# TLC5971.net
KiCad netlist of a schematic drawn in EAGLE
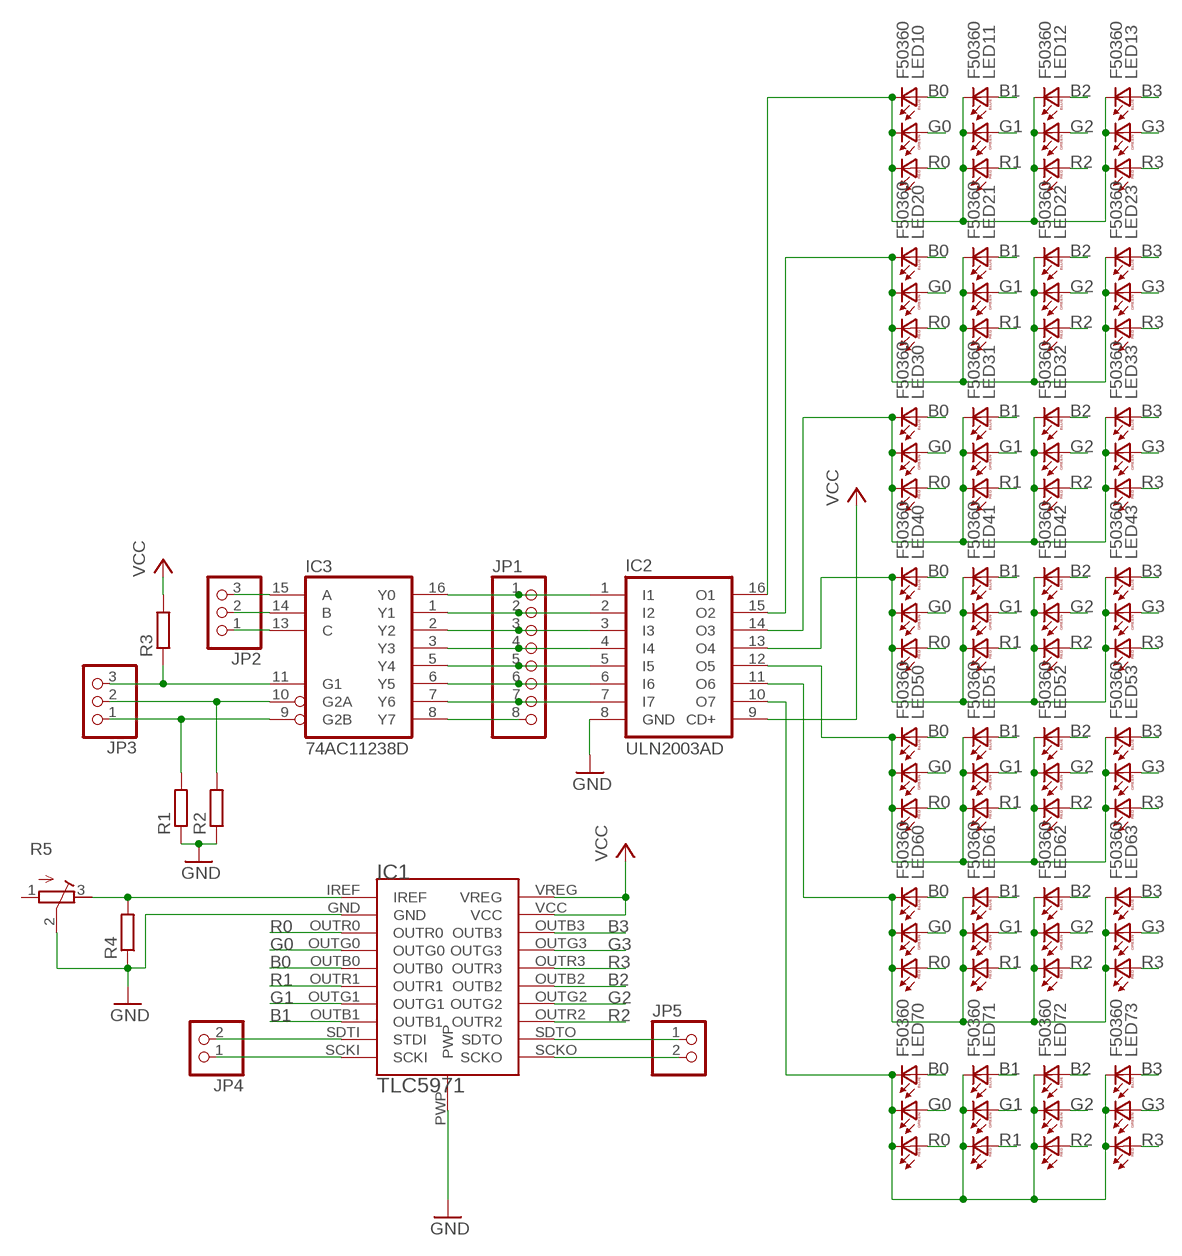
[diagram p0: schematic, sheet 1]

(export (version "E")
  (design (tool "Eeschema 10.0.6"))
  (components
    (comp (ref "IC1")
      (value "TLC5971")
      (footprint "eagle-import:HTSSOP-20(PWP)")
      (libsource (lib "eagle-import") (part "TLC5971"))
    )
    (comp (ref "IC2")
      (value "ULN2003AD")
      (footprint "eagle-import:SO16")
      (libsource (lib "eagle-import") (part "ULN2003AD"))
    )
    (comp (ref "IC3")
      (value "74AC11238D")
      (footprint "eagle-import:SO16")
      (libsource (lib "eagle-import") (part "74AC11238D"))
    )
    (comp (ref "JP1")
      (value "PINHD-1X8")
      (footprint "eagle-import:1X08")
      (libsource (lib "eagle-import") (part "PINHD-1X8"))
    )
    (comp (ref "JP2")
      (value "PINHD-1X3")
      (footprint "eagle-import:1X03")
      (libsource (lib "eagle-import") (part "PINHD-1X3"))
    )
    (comp (ref "JP3")
      (value "PINHD-1X3")
      (footprint "eagle-import:1X03")
      (libsource (lib "eagle-import") (part "PINHD-1X3"))
    )
    (comp (ref "JP4")
      (value "PINHD-1X2")
      (footprint "eagle-import:1X02")
      (libsource (lib "eagle-import") (part "PINHD-1X2"))
    )
    (comp (ref "JP5")
      (value "PINHD-1X2")
      (footprint "eagle-import:1X02")
      (libsource (lib "eagle-import") (part "PINHD-1X2"))
    )
    (comp (ref "LED10")
      (value "F50360")
      (footprint "eagle-import:F50360")
      (libsource (lib "eagle-import") (part "F50360"))
    )
    (comp (ref "LED11")
      (value "F50360")
      (footprint "eagle-import:F50360")
      (libsource (lib "eagle-import") (part "F50360"))
    )
    (comp (ref "LED12")
      (value "F50360")
      (footprint "eagle-import:F50360")
      (libsource (lib "eagle-import") (part "F50360"))
    )
    (comp (ref "LED13")
      (value "F50360")
      (footprint "eagle-import:F50360")
      (libsource (lib "eagle-import") (part "F50360"))
    )
    (comp (ref "LED20")
      (value "F50360")
      (footprint "eagle-import:F50360")
      (libsource (lib "eagle-import") (part "F50360"))
    )
    (comp (ref "LED21")
      (value "F50360")
      (footprint "eagle-import:F50360")
      (libsource (lib "eagle-import") (part "F50360"))
    )
    (comp (ref "LED22")
      (value "F50360")
      (footprint "eagle-import:F50360")
      (libsource (lib "eagle-import") (part "F50360"))
    )
    (comp (ref "LED23")
      (value "F50360")
      (footprint "eagle-import:F50360")
      (libsource (lib "eagle-import") (part "F50360"))
    )
    (comp (ref "LED30")
      (value "F50360")
      (footprint "eagle-import:F50360")
      (libsource (lib "eagle-import") (part "F50360"))
    )
    (comp (ref "LED31")
      (value "F50360")
      (footprint "eagle-import:F50360")
      (libsource (lib "eagle-import") (part "F50360"))
    )
    (comp (ref "LED32")
      (value "F50360")
      (footprint "eagle-import:F50360")
      (libsource (lib "eagle-import") (part "F50360"))
    )
    (comp (ref "LED33")
      (value "F50360")
      (footprint "eagle-import:F50360")
      (libsource (lib "eagle-import") (part "F50360"))
    )
    (comp (ref "LED40")
      (value "F50360")
      (footprint "eagle-import:F50360")
      (libsource (lib "eagle-import") (part "F50360"))
    )
    (comp (ref "LED41")
      (value "F50360")
      (footprint "eagle-import:F50360")
      (libsource (lib "eagle-import") (part "F50360"))
    )
    (comp (ref "LED42")
      (value "F50360")
      (footprint "eagle-import:F50360")
      (libsource (lib "eagle-import") (part "F50360"))
    )
    (comp (ref "LED43")
      (value "F50360")
      (footprint "eagle-import:F50360")
      (libsource (lib "eagle-import") (part "F50360"))
    )
    (comp (ref "LED50")
      (value "F50360")
      (footprint "eagle-import:F50360")
      (libsource (lib "eagle-import") (part "F50360"))
    )
    (comp (ref "LED51")
      (value "F50360")
      (footprint "eagle-import:F50360")
      (libsource (lib "eagle-import") (part "F50360"))
    )
    (comp (ref "LED52")
      (value "F50360")
      (footprint "eagle-import:F50360")
      (libsource (lib "eagle-import") (part "F50360"))
    )
    (comp (ref "LED53")
      (value "F50360")
      (footprint "eagle-import:F50360")
      (libsource (lib "eagle-import") (part "F50360"))
    )
    (comp (ref "LED60")
      (value "F50360")
      (footprint "eagle-import:F50360")
      (libsource (lib "eagle-import") (part "F50360"))
    )
    (comp (ref "LED61")
      (value "F50360")
      (footprint "eagle-import:F50360")
      (libsource (lib "eagle-import") (part "F50360"))
    )
    (comp (ref "LED62")
      (value "F50360")
      (footprint "eagle-import:F50360")
      (libsource (lib "eagle-import") (part "F50360"))
    )
    (comp (ref "LED63")
      (value "F50360")
      (footprint "eagle-import:F50360")
      (libsource (lib "eagle-import") (part "F50360"))
    )
    (comp (ref "LED70")
      (value "F50360")
      (footprint "eagle-import:F50360")
      (libsource (lib "eagle-import") (part "F50360"))
    )
    (comp (ref "LED71")
      (value "F50360")
      (footprint "eagle-import:F50360")
      (libsource (lib "eagle-import") (part "F50360"))
    )
    (comp (ref "LED72")
      (value "F50360")
      (footprint "eagle-import:F50360")
      (libsource (lib "eagle-import") (part "F50360"))
    )
    (comp (ref "LED73")
      (value "F50360")
      (footprint "eagle-import:F50360")
      (libsource (lib "eagle-import") (part "F50360"))
    )
    (comp (ref "R1")
      (value "R-EU_M0805")
      (footprint "eagle-import:M0805")
      (libsource (lib "eagle-import") (part "R-EU_M0805"))
    )
    (comp (ref "R2")
      (value "R-EU_M0805")
      (footprint "eagle-import:M0805")
      (libsource (lib "eagle-import") (part "R-EU_M0805"))
    )
    (comp (ref "R3")
      (value "R-EU_M0805")
      (footprint "eagle-import:M0805")
      (libsource (lib "eagle-import") (part "R-EU_M0805"))
    )
    (comp (ref "R4")
      (value "R-EU_M0805")
      (footprint "eagle-import:M0805")
      (libsource (lib "eagle-import") (part "R-EU_M0805"))
    )
    (comp (ref "R5")
      (value "R-TRIMM74W")
      (footprint "eagle-import:RTRIM74W")
      (libsource (lib "eagle-import") (part "R-TRIMM74W"))
    )
  )
  (nets
    (net (code "1") (name "/B0") (class "Default")
      (node (ref "IC1") (pin "OUTB0") (pinfunction "OUTB0_OUTB0") (pintype "output"))
      (node (ref "LED10") (pin "BA") (pinfunction "BA_BA") (pintype "passive"))
      (node (ref "LED20") (pin "BA") (pinfunction "BA_BA") (pintype "passive"))
      (node (ref "LED30") (pin "BA") (pinfunction "BA_BA") (pintype "passive"))
      (node (ref "LED40") (pin "BA") (pinfunction "BA_BA") (pintype "passive"))
      (node (ref "LED50") (pin "BA") (pinfunction "BA_BA") (pintype "passive"))
      (node (ref "LED60") (pin "BA") (pinfunction "BA_BA") (pintype "passive"))
      (node (ref "LED70") (pin "BA") (pinfunction "BA_BA") (pintype "passive"))
    )
    (net (code "2") (name "/B1") (class "Default")
      (node (ref "IC1") (pin "OUTB1") (pinfunction "OUTB1_OUTB1") (pintype "output"))
      (node (ref "LED11") (pin "BA") (pinfunction "BA_BA") (pintype "passive"))
      (node (ref "LED21") (pin "BA") (pinfunction "BA_BA") (pintype "passive"))
      (node (ref "LED31") (pin "BA") (pinfunction "BA_BA") (pintype "passive"))
      (node (ref "LED41") (pin "BA") (pinfunction "BA_BA") (pintype "passive"))
      (node (ref "LED51") (pin "BA") (pinfunction "BA_BA") (pintype "passive"))
      (node (ref "LED61") (pin "BA") (pinfunction "BA_BA") (pintype "passive"))
      (node (ref "LED71") (pin "BA") (pinfunction "BA_BA") (pintype "passive"))
    )
    (net (code "3") (name "/B2") (class "Default")
      (node (ref "IC1") (pin "OUTB2") (pinfunction "OUTB2_OUTB2") (pintype "output"))
      (node (ref "LED12") (pin "BA") (pinfunction "BA_BA") (pintype "passive"))
      (node (ref "LED22") (pin "BA") (pinfunction "BA_BA") (pintype "passive"))
      (node (ref "LED32") (pin "BA") (pinfunction "BA_BA") (pintype "passive"))
      (node (ref "LED42") (pin "BA") (pinfunction "BA_BA") (pintype "passive"))
      (node (ref "LED52") (pin "BA") (pinfunction "BA_BA") (pintype "passive"))
      (node (ref "LED62") (pin "BA") (pinfunction "BA_BA") (pintype "passive"))
      (node (ref "LED72") (pin "BA") (pinfunction "BA_BA") (pintype "passive"))
    )
    (net (code "4") (name "/B3") (class "Default")
      (node (ref "IC1") (pin "OUTB3") (pinfunction "OUTB3_OUTB3") (pintype "output"))
      (node (ref "LED13") (pin "BA") (pinfunction "BA_BA") (pintype "passive"))
      (node (ref "LED23") (pin "BA") (pinfunction "BA_BA") (pintype "passive"))
      (node (ref "LED33") (pin "BA") (pinfunction "BA_BA") (pintype "passive"))
      (node (ref "LED43") (pin "BA") (pinfunction "BA_BA") (pintype "passive"))
      (node (ref "LED53") (pin "BA") (pinfunction "BA_BA") (pintype "passive"))
      (node (ref "LED63") (pin "BA") (pinfunction "BA_BA") (pintype "passive"))
      (node (ref "LED73") (pin "BA") (pinfunction "BA_BA") (pintype "passive"))
    )
    (net (code "5") (name "/G0") (class "Default")
      (node (ref "IC1") (pin "OUTG0") (pinfunction "OUTG0_OUTG0") (pintype "output"))
      (node (ref "LED10") (pin "GA") (pinfunction "GA_GA") (pintype "passive"))
      (node (ref "LED20") (pin "GA") (pinfunction "GA_GA") (pintype "passive"))
      (node (ref "LED30") (pin "GA") (pinfunction "GA_GA") (pintype "passive"))
      (node (ref "LED40") (pin "GA") (pinfunction "GA_GA") (pintype "passive"))
      (node (ref "LED50") (pin "GA") (pinfunction "GA_GA") (pintype "passive"))
      (node (ref "LED60") (pin "GA") (pinfunction "GA_GA") (pintype "passive"))
      (node (ref "LED70") (pin "GA") (pinfunction "GA_GA") (pintype "passive"))
    )
    (net (code "6") (name "/G1") (class "Default")
      (node (ref "IC1") (pin "OUTG1") (pinfunction "OUTG1_OUTG1") (pintype "output"))
      (node (ref "LED11") (pin "GA") (pinfunction "GA_GA") (pintype "passive"))
      (node (ref "LED21") (pin "GA") (pinfunction "GA_GA") (pintype "passive"))
      (node (ref "LED31") (pin "GA") (pinfunction "GA_GA") (pintype "passive"))
      (node (ref "LED41") (pin "GA") (pinfunction "GA_GA") (pintype "passive"))
      (node (ref "LED51") (pin "GA") (pinfunction "GA_GA") (pintype "passive"))
      (node (ref "LED61") (pin "GA") (pinfunction "GA_GA") (pintype "passive"))
      (node (ref "LED71") (pin "GA") (pinfunction "GA_GA") (pintype "passive"))
    )
    (net (code "7") (name "/G2") (class "Default")
      (node (ref "IC1") (pin "OUTG2") (pinfunction "OUTG2_OUTG2") (pintype "output"))
      (node (ref "LED12") (pin "GA") (pinfunction "GA_GA") (pintype "passive"))
      (node (ref "LED22") (pin "GA") (pinfunction "GA_GA") (pintype "passive"))
      (node (ref "LED32") (pin "GA") (pinfunction "GA_GA") (pintype "passive"))
      (node (ref "LED42") (pin "GA") (pinfunction "GA_GA") (pintype "passive"))
      (node (ref "LED52") (pin "GA") (pinfunction "GA_GA") (pintype "passive"))
      (node (ref "LED62") (pin "GA") (pinfunction "GA_GA") (pintype "passive"))
      (node (ref "LED72") (pin "GA") (pinfunction "GA_GA") (pintype "passive"))
    )
    (net (code "8") (name "/G3") (class "Default")
      (node (ref "IC1") (pin "OUTG3") (pinfunction "OUTG3_OUTG3") (pintype "output"))
      (node (ref "LED13") (pin "GA") (pinfunction "GA_GA") (pintype "passive"))
      (node (ref "LED23") (pin "GA") (pinfunction "GA_GA") (pintype "passive"))
      (node (ref "LED33") (pin "GA") (pinfunction "GA_GA") (pintype "passive"))
      (node (ref "LED43") (pin "GA") (pinfunction "GA_GA") (pintype "passive"))
      (node (ref "LED53") (pin "GA") (pinfunction "GA_GA") (pintype "passive"))
      (node (ref "LED63") (pin "GA") (pinfunction "GA_GA") (pintype "passive"))
      (node (ref "LED73") (pin "GA") (pinfunction "GA_GA") (pintype "passive"))
    )
    (net (code "9") (name "/R0") (class "Default")
      (node (ref "IC1") (pin "OUTR0") (pinfunction "OUTR0_OUTR0") (pintype "output"))
      (node (ref "LED10") (pin "RA") (pinfunction "RA_RA") (pintype "passive"))
      (node (ref "LED20") (pin "RA") (pinfunction "RA_RA") (pintype "passive"))
      (node (ref "LED30") (pin "RA") (pinfunction "RA_RA") (pintype "passive"))
      (node (ref "LED40") (pin "RA") (pinfunction "RA_RA") (pintype "passive"))
      (node (ref "LED50") (pin "RA") (pinfunction "RA_RA") (pintype "passive"))
      (node (ref "LED60") (pin "RA") (pinfunction "RA_RA") (pintype "passive"))
      (node (ref "LED70") (pin "RA") (pinfunction "RA_RA") (pintype "passive"))
    )
    (net (code "10") (name "/R1") (class "Default")
      (node (ref "IC1") (pin "OUTR1") (pinfunction "OUTR1_OUTR1") (pintype "output"))
      (node (ref "LED11") (pin "RA") (pinfunction "RA_RA") (pintype "passive"))
      (node (ref "LED21") (pin "RA") (pinfunction "RA_RA") (pintype "passive"))
      (node (ref "LED31") (pin "RA") (pinfunction "RA_RA") (pintype "passive"))
      (node (ref "LED41") (pin "RA") (pinfunction "RA_RA") (pintype "passive"))
      (node (ref "LED51") (pin "RA") (pinfunction "RA_RA") (pintype "passive"))
      (node (ref "LED61") (pin "RA") (pinfunction "RA_RA") (pintype "passive"))
      (node (ref "LED71") (pin "RA") (pinfunction "RA_RA") (pintype "passive"))
    )
    (net (code "11") (name "/R2") (class "Default")
      (node (ref "IC1") (pin "OUTR2") (pinfunction "OUTR2_OUTR2") (pintype "output"))
      (node (ref "LED12") (pin "RA") (pinfunction "RA_RA") (pintype "passive"))
      (node (ref "LED22") (pin "RA") (pinfunction "RA_RA") (pintype "passive"))
      (node (ref "LED32") (pin "RA") (pinfunction "RA_RA") (pintype "passive"))
      (node (ref "LED42") (pin "RA") (pinfunction "RA_RA") (pintype "passive"))
      (node (ref "LED52") (pin "RA") (pinfunction "RA_RA") (pintype "passive"))
      (node (ref "LED62") (pin "RA") (pinfunction "RA_RA") (pintype "passive"))
      (node (ref "LED72") (pin "RA") (pinfunction "RA_RA") (pintype "passive"))
    )
    (net (code "12") (name "/R3") (class "Default")
      (node (ref "IC1") (pin "OUTR3") (pinfunction "OUTR3_OUTR3") (pintype "bidirectional"))
      (node (ref "LED13") (pin "RA") (pinfunction "RA_RA") (pintype "passive"))
      (node (ref "LED23") (pin "RA") (pinfunction "RA_RA") (pintype "passive"))
      (node (ref "LED33") (pin "RA") (pinfunction "RA_RA") (pintype "passive"))
      (node (ref "LED43") (pin "RA") (pinfunction "RA_RA") (pintype "passive"))
      (node (ref "LED53") (pin "RA") (pinfunction "RA_RA") (pintype "passive"))
      (node (ref "LED63") (pin "RA") (pinfunction "RA_RA") (pintype "passive"))
      (node (ref "LED73") (pin "RA") (pinfunction "RA_RA") (pintype "passive"))
    )
    (net (code "13") (name "GND") (class "Default")
      (node (ref "IC1") (pin "GND") (pinfunction "GND_GND") (pintype "power_in"))
      (node (ref "IC1") (pin "PWP") (pinfunction "PWP_PWP") (pintype "bidirectional"))
      (node (ref "IC2") (pin "8") (pinfunction "GND_8") (pintype "power_in"))
      (node (ref "R1") (pin "1") (pinfunction "1_1") (pintype "passive"))
      (node (ref "R2") (pin "1") (pinfunction "1_1") (pintype "passive"))
      (node (ref "R4") (pin "1") (pinfunction "1_1") (pintype "passive"))
      (node (ref "R5") (pin "2") (pinfunction "S_2") (pintype "passive"))
    )
    (net (code "14") (name "Net-(IC1-PadSCKI)") (class "Default")
      (node (ref "IC1") (pin "SCKI") (pinfunction "SCKI_SCKI") (pintype "bidirectional"))
      (node (ref "JP4") (pin "1") (pinfunction "1_1") (pintype "passive"))
    )
    (net (code "15") (name "Net-(IC1-PadSCKO)") (class "Default")
      (node (ref "IC1") (pin "SCKO") (pinfunction "SCKO_SCKO") (pintype "bidirectional"))
      (node (ref "JP5") (pin "2") (pinfunction "2_2") (pintype "passive"))
    )
    (net (code "16") (name "Net-(IC1-PadSDTO)") (class "Default")
      (node (ref "IC1") (pin "SDTO") (pinfunction "SDTO_SDTO") (pintype "bidirectional"))
      (node (ref "JP5") (pin "1") (pinfunction "1_1") (pintype "passive"))
    )
    (net (code "17") (name "Net-(IC1-STDI)") (class "Default")
      (node (ref "IC1") (pin "SDTI") (pinfunction "STDI_SDTI") (pintype "bidirectional"))
      (node (ref "JP4") (pin "2") (pinfunction "2_2") (pintype "passive"))
    )
    (net (code "18") (name "Net-(IC2-I1)") (class "Default")
      (node (ref "IC2") (pin "1") (pinfunction "I1_1") (pintype "input"))
      (node (ref "IC3") (pin "16") (pinfunction "Y0_16") (pintype "output"))
      (node (ref "JP1") (pin "1") (pinfunction "1_1") (pintype "passive"))
    )
    (net (code "19") (name "Net-(IC2-I2)") (class "Default")
      (node (ref "IC2") (pin "2") (pinfunction "I2_2") (pintype "input"))
      (node (ref "IC3") (pin "1") (pinfunction "Y1_1") (pintype "output"))
      (node (ref "JP1") (pin "2") (pinfunction "2_2") (pintype "passive"))
    )
    (net (code "20") (name "Net-(IC2-I3)") (class "Default")
      (node (ref "IC2") (pin "3") (pinfunction "I3_3") (pintype "input"))
      (node (ref "IC3") (pin "2") (pinfunction "Y2_2") (pintype "output"))
      (node (ref "JP1") (pin "3") (pinfunction "3_3") (pintype "passive"))
    )
    (net (code "21") (name "Net-(IC2-I4)") (class "Default")
      (node (ref "IC2") (pin "4") (pinfunction "I4_4") (pintype "input"))
      (node (ref "IC3") (pin "3") (pinfunction "Y3_3") (pintype "output"))
      (node (ref "JP1") (pin "4") (pinfunction "4_4") (pintype "passive"))
    )
    (net (code "22") (name "Net-(IC2-I5)") (class "Default")
      (node (ref "IC2") (pin "5") (pinfunction "I5_5") (pintype "input"))
      (node (ref "IC3") (pin "5") (pinfunction "Y4_5") (pintype "output"))
      (node (ref "JP1") (pin "5") (pinfunction "5_5") (pintype "passive"))
    )
    (net (code "23") (name "Net-(IC2-I6)") (class "Default")
      (node (ref "IC2") (pin "6") (pinfunction "I6_6") (pintype "input"))
      (node (ref "IC3") (pin "6") (pinfunction "Y5_6") (pintype "output"))
      (node (ref "JP1") (pin "6") (pinfunction "6_6") (pintype "passive"))
    )
    (net (code "24") (name "Net-(IC2-I7)") (class "Default")
      (node (ref "IC2") (pin "7") (pinfunction "I7_7") (pintype "input"))
      (node (ref "IC3") (pin "7") (pinfunction "Y6_7") (pintype "output"))
      (node (ref "JP1") (pin "7") (pinfunction "7_7") (pintype "passive"))
    )
    (net (code "25") (name "Net-(IC2-O1)") (class "Default")
      (node (ref "IC2") (pin "16") (pinfunction "O1_16") (pintype "open_collector"))
      (node (ref "LED10") (pin "BC") (pinfunction "BC_BC") (pintype "passive"))
      (node (ref "LED10") (pin "GC") (pinfunction "GC_GC") (pintype "passive"))
      (node (ref "LED10") (pin "RC") (pinfunction "RC_RC") (pintype "passive"))
      (node (ref "LED11") (pin "BC") (pinfunction "BC_BC") (pintype "passive"))
      (node (ref "LED11") (pin "GC") (pinfunction "GC_GC") (pintype "passive"))
      (node (ref "LED11") (pin "RC") (pinfunction "RC_RC") (pintype "passive"))
      (node (ref "LED12") (pin "BC") (pinfunction "BC_BC") (pintype "passive"))
      (node (ref "LED12") (pin "GC") (pinfunction "GC_GC") (pintype "passive"))
      (node (ref "LED12") (pin "RC") (pinfunction "RC_RC") (pintype "passive"))
      (node (ref "LED13") (pin "BC") (pinfunction "BC_BC") (pintype "passive"))
      (node (ref "LED13") (pin "GC") (pinfunction "GC_GC") (pintype "passive"))
      (node (ref "LED13") (pin "RC") (pinfunction "RC_RC") (pintype "passive"))
    )
    (net (code "26") (name "Net-(IC2-O2)") (class "Default")
      (node (ref "IC2") (pin "15") (pinfunction "O2_15") (pintype "open_collector"))
      (node (ref "LED20") (pin "BC") (pinfunction "BC_BC") (pintype "passive"))
      (node (ref "LED20") (pin "GC") (pinfunction "GC_GC") (pintype "passive"))
      (node (ref "LED20") (pin "RC") (pinfunction "RC_RC") (pintype "passive"))
      (node (ref "LED21") (pin "BC") (pinfunction "BC_BC") (pintype "passive"))
      (node (ref "LED21") (pin "GC") (pinfunction "GC_GC") (pintype "passive"))
      (node (ref "LED21") (pin "RC") (pinfunction "RC_RC") (pintype "passive"))
      (node (ref "LED22") (pin "BC") (pinfunction "BC_BC") (pintype "passive"))
      (node (ref "LED22") (pin "GC") (pinfunction "GC_GC") (pintype "passive"))
      (node (ref "LED22") (pin "RC") (pinfunction "RC_RC") (pintype "passive"))
      (node (ref "LED23") (pin "BC") (pinfunction "BC_BC") (pintype "passive"))
      (node (ref "LED23") (pin "GC") (pinfunction "GC_GC") (pintype "passive"))
      (node (ref "LED23") (pin "RC") (pinfunction "RC_RC") (pintype "passive"))
    )
    (net (code "27") (name "Net-(IC2-O3)") (class "Default")
      (node (ref "IC2") (pin "14") (pinfunction "O3_14") (pintype "open_collector"))
      (node (ref "LED30") (pin "BC") (pinfunction "BC_BC") (pintype "passive"))
      (node (ref "LED30") (pin "GC") (pinfunction "GC_GC") (pintype "passive"))
      (node (ref "LED30") (pin "RC") (pinfunction "RC_RC") (pintype "passive"))
      (node (ref "LED31") (pin "BC") (pinfunction "BC_BC") (pintype "passive"))
      (node (ref "LED31") (pin "GC") (pinfunction "GC_GC") (pintype "passive"))
      (node (ref "LED31") (pin "RC") (pinfunction "RC_RC") (pintype "passive"))
      (node (ref "LED32") (pin "BC") (pinfunction "BC_BC") (pintype "passive"))
      (node (ref "LED32") (pin "GC") (pinfunction "GC_GC") (pintype "passive"))
      (node (ref "LED32") (pin "RC") (pinfunction "RC_RC") (pintype "passive"))
      (node (ref "LED33") (pin "BC") (pinfunction "BC_BC") (pintype "passive"))
      (node (ref "LED33") (pin "GC") (pinfunction "GC_GC") (pintype "passive"))
      (node (ref "LED33") (pin "RC") (pinfunction "RC_RC") (pintype "passive"))
    )
    (net (code "28") (name "Net-(IC2-O4)") (class "Default")
      (node (ref "IC2") (pin "13") (pinfunction "O4_13") (pintype "open_collector"))
      (node (ref "LED40") (pin "BC") (pinfunction "BC_BC") (pintype "passive"))
      (node (ref "LED40") (pin "GC") (pinfunction "GC_GC") (pintype "passive"))
      (node (ref "LED40") (pin "RC") (pinfunction "RC_RC") (pintype "passive"))
      (node (ref "LED41") (pin "BC") (pinfunction "BC_BC") (pintype "passive"))
      (node (ref "LED41") (pin "GC") (pinfunction "GC_GC") (pintype "passive"))
      (node (ref "LED41") (pin "RC") (pinfunction "RC_RC") (pintype "passive"))
      (node (ref "LED42") (pin "BC") (pinfunction "BC_BC") (pintype "passive"))
      (node (ref "LED42") (pin "GC") (pinfunction "GC_GC") (pintype "passive"))
      (node (ref "LED42") (pin "RC") (pinfunction "RC_RC") (pintype "passive"))
      (node (ref "LED43") (pin "BC") (pinfunction "BC_BC") (pintype "passive"))
      (node (ref "LED43") (pin "GC") (pinfunction "GC_GC") (pintype "passive"))
      (node (ref "LED43") (pin "RC") (pinfunction "RC_RC") (pintype "passive"))
    )
    (net (code "29") (name "Net-(IC2-O5)") (class "Default")
      (node (ref "IC2") (pin "12") (pinfunction "O5_12") (pintype "open_collector"))
      (node (ref "LED50") (pin "BC") (pinfunction "BC_BC") (pintype "passive"))
      (node (ref "LED50") (pin "GC") (pinfunction "GC_GC") (pintype "passive"))
      (node (ref "LED50") (pin "RC") (pinfunction "RC_RC") (pintype "passive"))
      (node (ref "LED51") (pin "BC") (pinfunction "BC_BC") (pintype "passive"))
      (node (ref "LED51") (pin "GC") (pinfunction "GC_GC") (pintype "passive"))
      (node (ref "LED51") (pin "RC") (pinfunction "RC_RC") (pintype "passive"))
      (node (ref "LED52") (pin "BC") (pinfunction "BC_BC") (pintype "passive"))
      (node (ref "LED52") (pin "GC") (pinfunction "GC_GC") (pintype "passive"))
      (node (ref "LED52") (pin "RC") (pinfunction "RC_RC") (pintype "passive"))
      (node (ref "LED53") (pin "BC") (pinfunction "BC_BC") (pintype "passive"))
      (node (ref "LED53") (pin "GC") (pinfunction "GC_GC") (pintype "passive"))
      (node (ref "LED53") (pin "RC") (pinfunction "RC_RC") (pintype "passive"))
    )
    (net (code "30") (name "Net-(IC2-O6)") (class "Default")
      (node (ref "IC2") (pin "11") (pinfunction "O6_11") (pintype "open_collector"))
      (node (ref "LED60") (pin "BC") (pinfunction "BC_BC") (pintype "passive"))
      (node (ref "LED60") (pin "GC") (pinfunction "GC_GC") (pintype "passive"))
      (node (ref "LED60") (pin "RC") (pinfunction "RC_RC") (pintype "passive"))
      (node (ref "LED61") (pin "BC") (pinfunction "BC_BC") (pintype "passive"))
      (node (ref "LED61") (pin "GC") (pinfunction "GC_GC") (pintype "passive"))
      (node (ref "LED61") (pin "RC") (pinfunction "RC_RC") (pintype "passive"))
      (node (ref "LED62") (pin "BC") (pinfunction "BC_BC") (pintype "passive"))
      (node (ref "LED62") (pin "GC") (pinfunction "GC_GC") (pintype "passive"))
      (node (ref "LED62") (pin "RC") (pinfunction "RC_RC") (pintype "passive"))
      (node (ref "LED63") (pin "BC") (pinfunction "BC_BC") (pintype "passive"))
      (node (ref "LED63") (pin "GC") (pinfunction "GC_GC") (pintype "passive"))
      (node (ref "LED63") (pin "RC") (pinfunction "RC_RC") (pintype "passive"))
    )
    (net (code "31") (name "Net-(IC2-O7)") (class "Default")
      (node (ref "IC2") (pin "10") (pinfunction "O7_10") (pintype "open_collector"))
      (node (ref "LED70") (pin "BC") (pinfunction "BC_BC") (pintype "passive"))
      (node (ref "LED70") (pin "GC") (pinfunction "GC_GC") (pintype "passive"))
      (node (ref "LED70") (pin "RC") (pinfunction "RC_RC") (pintype "passive"))
      (node (ref "LED71") (pin "BC") (pinfunction "BC_BC") (pintype "passive"))
      (node (ref "LED71") (pin "GC") (pinfunction "GC_GC") (pintype "passive"))
      (node (ref "LED71") (pin "RC") (pinfunction "RC_RC") (pintype "passive"))
      (node (ref "LED72") (pin "BC") (pinfunction "BC_BC") (pintype "passive"))
      (node (ref "LED72") (pin "GC") (pinfunction "GC_GC") (pintype "passive"))
      (node (ref "LED72") (pin "RC") (pinfunction "RC_RC") (pintype "passive"))
      (node (ref "LED73") (pin "BC") (pinfunction "BC_BC") (pintype "passive"))
      (node (ref "LED73") (pin "GC") (pinfunction "GC_GC") (pintype "passive"))
      (node (ref "LED73") (pin "RC") (pinfunction "RC_RC") (pintype "passive"))
    )
    (net (code "32") (name "Net-(IC3A-A)") (class "Default")
      (node (ref "IC3") (pin "15") (pinfunction "A_15") (pintype "input"))
      (node (ref "JP2") (pin "3") (pinfunction "3_3") (pintype "passive"))
    )
    (net (code "33") (name "Net-(IC3A-B)") (class "Default")
      (node (ref "IC3") (pin "14") (pinfunction "B_14") (pintype "input"))
      (node (ref "JP2") (pin "2") (pinfunction "2_2") (pintype "passive"))
    )
    (net (code "34") (name "Net-(IC3A-C)") (class "Default")
      (node (ref "IC3") (pin "13") (pinfunction "C_13") (pintype "input"))
      (node (ref "JP2") (pin "1") (pinfunction "1_1") (pintype "passive"))
    )
    (net (code "35") (name "Net-(IC3A-G1)") (class "Default")
      (node (ref "IC3") (pin "11") (pinfunction "G1_11") (pintype "input"))
      (node (ref "JP3") (pin "3") (pinfunction "3_3") (pintype "passive"))
      (node (ref "R3") (pin "1") (pinfunction "1_1") (pintype "passive"))
    )
    (net (code "36") (name "Net-(IC3A-G2A)") (class "Default")
      (node (ref "IC3") (pin "10") (pinfunction "G2A_10") (pintype "input"))
      (node (ref "JP3") (pin "2") (pinfunction "2_2") (pintype "passive"))
      (node (ref "R2") (pin "2") (pinfunction "2_2") (pintype "passive"))
    )
    (net (code "37") (name "Net-(IC3A-G2B)") (class "Default")
      (node (ref "IC3") (pin "9") (pinfunction "G2B_9") (pintype "input"))
      (node (ref "JP3") (pin "1") (pinfunction "1_1") (pintype "passive"))
      (node (ref "R1") (pin "2") (pinfunction "2_2") (pintype "passive"))
    )
    (net (code "38") (name "Net-(IC3A-Y7)") (class "Default")
      (node (ref "IC3") (pin "8") (pinfunction "Y7_8") (pintype "output"))
      (node (ref "JP1") (pin "8") (pinfunction "8_8") (pintype "passive"))
    )
    (net (code "39") (name "Net-(R5-E)") (class "Default")
      (node (ref "IC1") (pin "IREF") (pinfunction "IREF_IREF") (pintype "input"))
      (node (ref "R4") (pin "2") (pinfunction "2_2") (pintype "passive"))
      (node (ref "R5") (pin "3") (pinfunction "E_3") (pintype "passive"))
    )
    (net (code "40") (name "VCC") (class "Default")
      (node (ref "IC1") (pin "VCC") (pinfunction "VCC_VCC") (pintype "power_in"))
      (node (ref "IC1") (pin "VREG") (pinfunction "VREG_VREG") (pintype "power_in"))
      (node (ref "IC2") (pin "9") (pinfunction "CD+_9") (pintype "passive"))
      (node (ref "R3") (pin "2") (pinfunction "2_2") (pintype "passive"))
    )
    (net (code "41") (name "unconnected-(R5-A-Pad1)") (class "Default")
      (node (ref "R5") (pin "1") (pinfunction "A_1") (pintype "passive"))
    )
  )
)
